# Power.net
KiCad netlist of a schematic drawn in Altium Designer
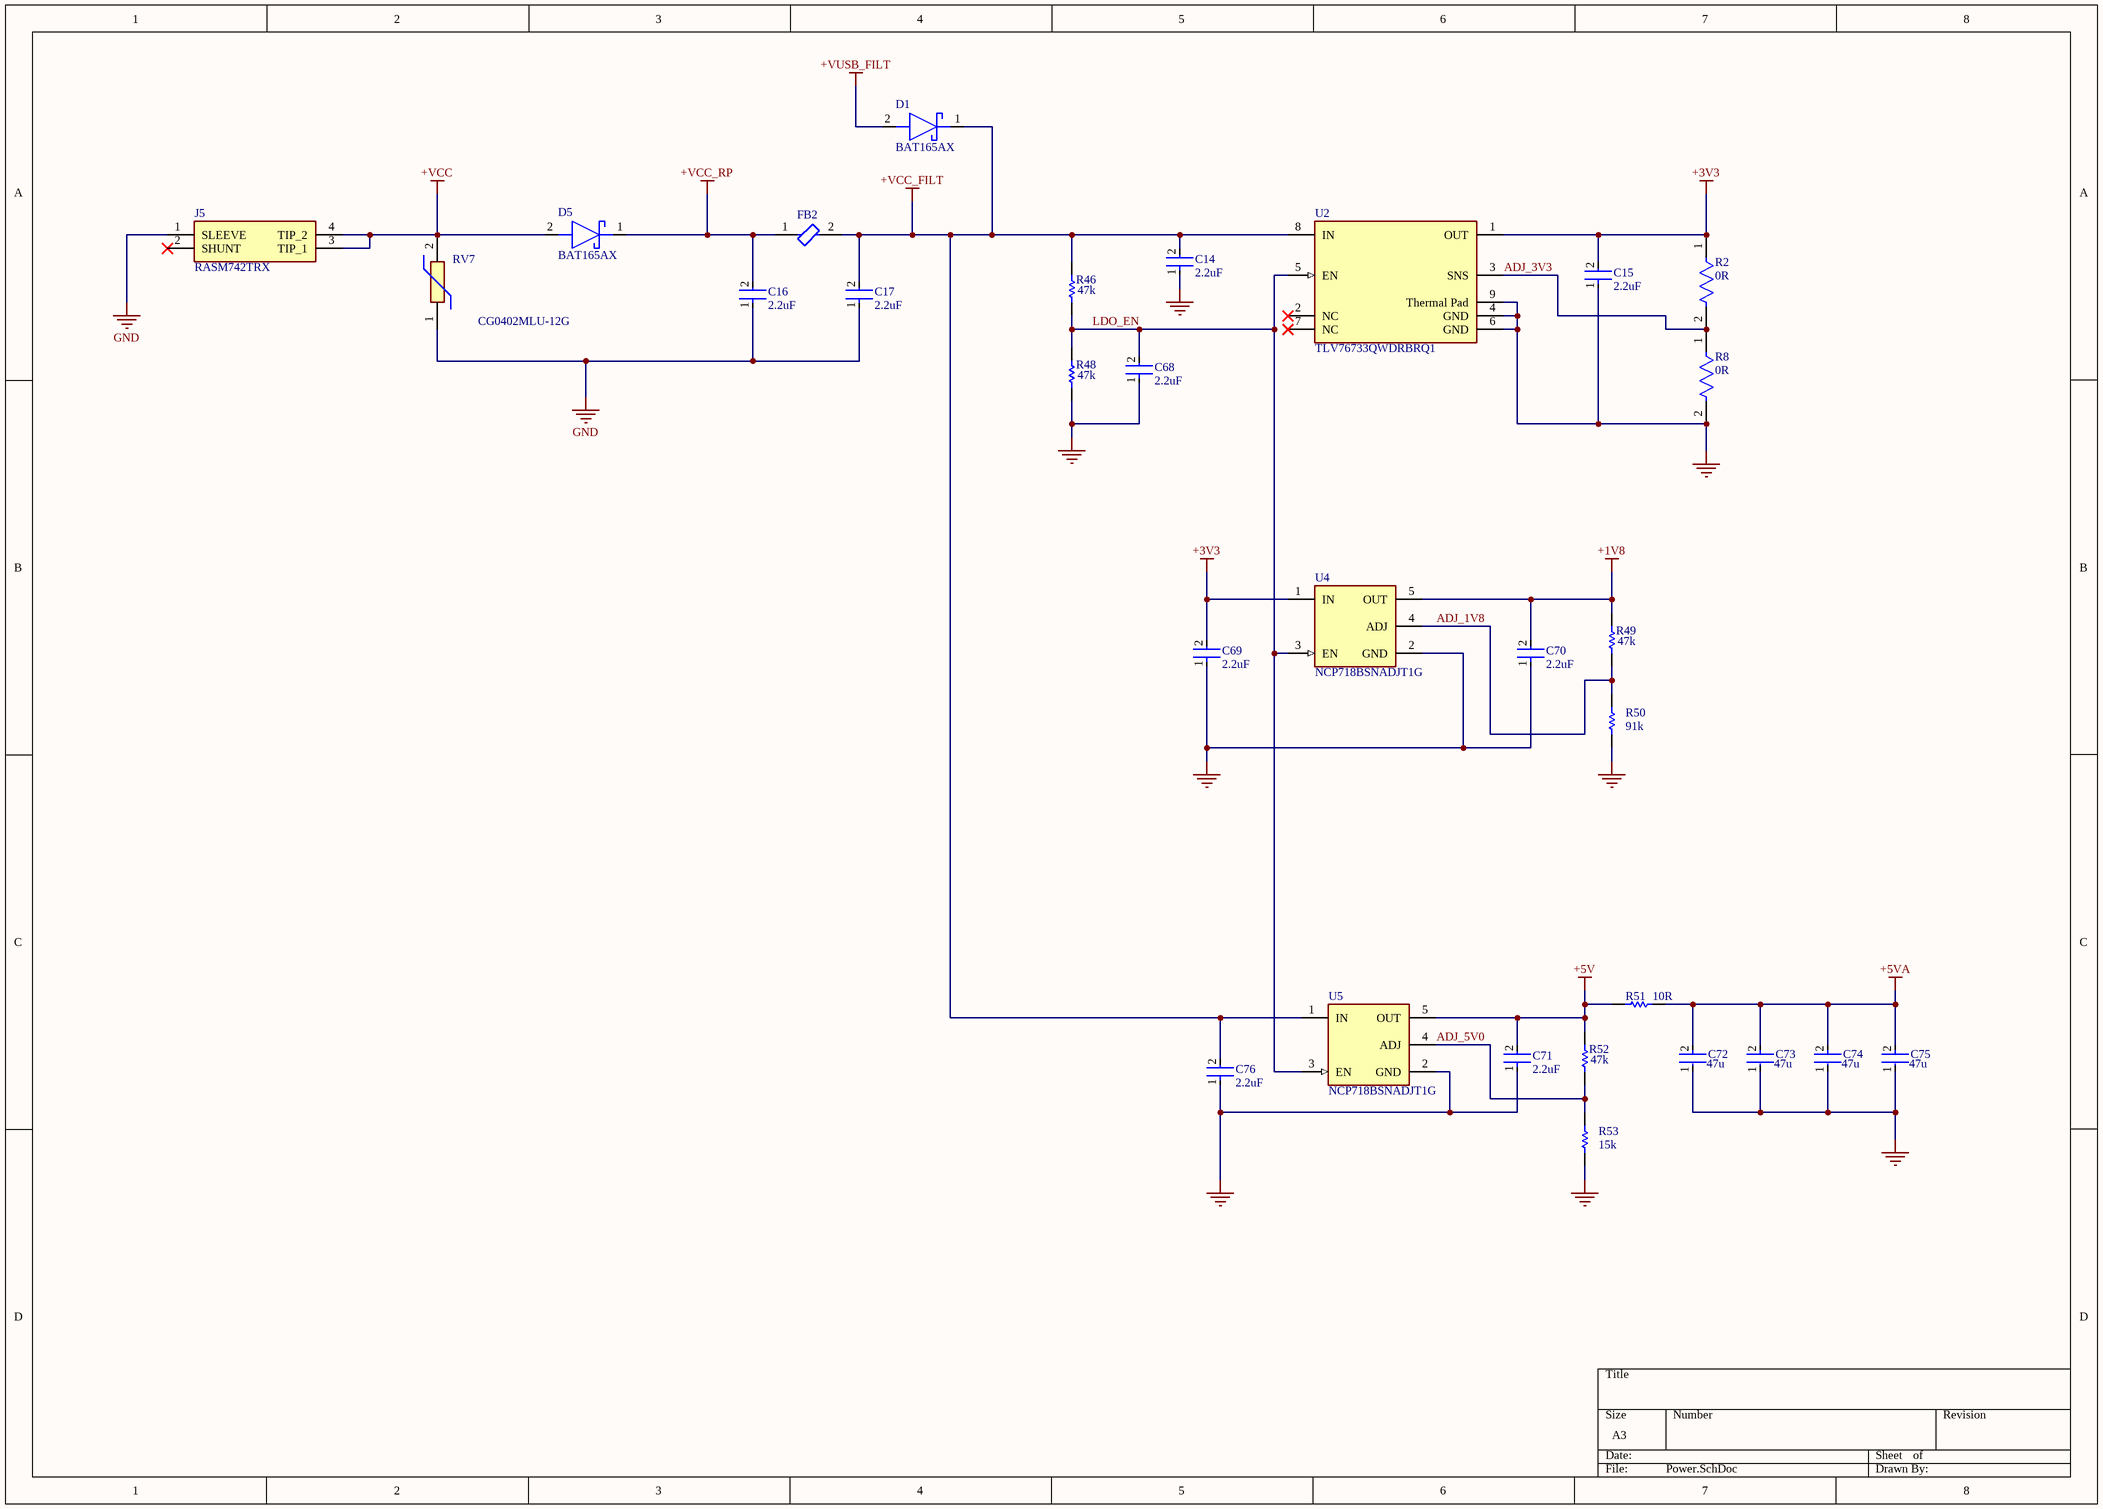
[diagram p0: Power.SchDoc]

(export (version "E")
  (design (tool "Eeschema 10.0.6"))
  (components
    (comp (ref "C14")
      (value "GCM188C71A225KE02D")
      (footprint "FP-GCH188-0_1-e0_2_0_5-MFG")
      (description "GCM188C71A225KE02D Multilayer Ceramic Capacitor, 2.2 uF, 10 V, ± 10%, X7S, 0603 [1608 Metric]")
      (fields (field (name "CAPACITANCE") "2.2uF"))
      (libsource (lib "Altium Content Vault") (part "b4654b650e69147ec39a6b967a45e02"))
    )
    (comp (ref "C15")
      (value "GCM188C71A225KE02D")
      (footprint "FP-GCH188-0_1-e0_2_0_5-MFG")
      (description "GCM188C71A225KE02D Multilayer Ceramic Capacitor, 2.2 uF, 10 V, ± 10%, X7S, 0603 [1608 Metric]")
      (fields (field (name "CAPACITANCE") "2.2uF"))
      (libsource (lib "Altium Content Vault") (part "b4654b650e69147ec39a6b967a45e02"))
    )
    (comp (ref "C16")
      (value "GCM188C71A225KE02D")
      (footprint "FP-GCH188-0_1-e0_2_0_5-MFG")
      (description "GCM188C71A225KE02D Multilayer Ceramic Capacitor, 2.2 uF, 10 V, ± 10%, X7S, 0603 [1608 Metric]")
      (fields (field (name "CAPACITANCE") "2.2uF"))
      (libsource (lib "Altium Content Vault") (part "b4654b650e69147ec39a6b967a45e02"))
    )
    (comp (ref "C17")
      (value "GCM188C71A225KE02D")
      (footprint "FP-GCH188-0_1-e0_2_0_5-MFG")
      (description "GCM188C71A225KE02D Multilayer Ceramic Capacitor, 2.2 uF, 10 V, ± 10%, X7S, 0603 [1608 Metric]")
      (fields (field (name "CAPACITANCE") "2.2uF"))
      (libsource (lib "Altium Content Vault") (part "b4654b650e69147ec39a6b967a45e02"))
    )
    (comp (ref "C68")
      (value "GCM188C71A225KE02D")
      (footprint "FP-GCH188-0_1-e0_2_0_5-MFG")
      (description "GCM188C71A225KE02D Multilayer Ceramic Capacitor, 2.2 uF, 10 V, ± 10%, X7S, 0603 [1608 Metric]")
      (fields (field (name "CAPACITANCE") "2.2uF"))
      (libsource (lib "Altium Content Vault") (part "b4654b650e69147ec39a6b967a45e02"))
    )
    (comp (ref "C69")
      (value "GCM188C71A225KE02D")
      (footprint "FP-GCH188-0_1-e0_2_0_5-MFG")
      (description "GCM188C71A225KE02D Multilayer Ceramic Capacitor, 2.2 uF, 10 V, ± 10%, X7S, 0603 [1608 Metric]")
      (fields (field (name "CAPACITANCE") "2.2uF"))
      (libsource (lib "Altium Content Vault") (part "b4654b650e69147ec39a6b967a45e02"))
    )
    (comp (ref "C70")
      (value "GCM188C71A225KE02D")
      (footprint "FP-GCH188-0_1-e0_2_0_5-MFG")
      (description "GCM188C71A225KE02D Multilayer Ceramic Capacitor, 2.2 uF, 10 V, ± 10%, X7S, 0603 [1608 Metric]")
      (fields (field (name "CAPACITANCE") "2.2uF"))
      (libsource (lib "Altium Content Vault") (part "b4654b650e69147ec39a6b967a45e02"))
    )
    (comp (ref "C71")
      (value "GCM188C71A225KE02D")
      (footprint "FP-GCH188-0_1-e0_2_0_5-MFG")
      (description "GCM188C71A225KE02D Multilayer Ceramic Capacitor, 2.2 uF, 10 V, ± 10%, X7S, 0603 [1608 Metric]")
      (fields (field (name "CAPACITANCE") "2.2uF"))
      (libsource (lib "Altium Content Vault") (part "b4654b650e69147ec39a6b967a45e02"))
    )
    (comp (ref "C72")
      (value "GCM32EC71A476KE02K")
      (footprint "FP-GCM32E-0_3-MFG")
      (description "Ceramic Capacitor for Automotive 47uF ±10% 10VDC X7S 1210 Embossed T/R")
      (fields (field (name "CAPACITANCE") "47u"))
      (libsource (lib "Altium Content Vault") (part "f23184f103b6ebe33a8c269c53dcba6"))
    )
    (comp (ref "C73")
      (value "GCM32EC71A476KE02K")
      (footprint "FP-GCM32E-0_3-MFG")
      (description "Ceramic Capacitor for Automotive 47uF ±10% 10VDC X7S 1210 Embossed T/R")
      (fields (field (name "CAPACITANCE") "47u"))
      (libsource (lib "Altium Content Vault") (part "f23184f103b6ebe33a8c269c53dcba6"))
    )
    (comp (ref "C74")
      (value "GCM32EC71A476KE02K")
      (footprint "FP-GCM32E-0_3-MFG")
      (description "Ceramic Capacitor for Automotive 47uF ±10% 10VDC X7S 1210 Embossed T/R")
      (fields (field (name "CAPACITANCE") "47u"))
      (libsource (lib "Altium Content Vault") (part "f23184f103b6ebe33a8c269c53dcba6"))
    )
    (comp (ref "C75")
      (value "GCM32EC71A476KE02K")
      (footprint "FP-GCM32E-0_3-MFG")
      (description "Ceramic Capacitor for Automotive 47uF ±10% 10VDC X7S 1210 Embossed T/R")
      (fields (field (name "CAPACITANCE") "47u"))
      (libsource (lib "Altium Content Vault") (part "f23184f103b6ebe33a8c269c53dcba6"))
    )
    (comp (ref "C76")
      (value "GCM188C71A225KE02D")
      (footprint "FP-GCH188-0_1-e0_2_0_5-MFG")
      (description "GCM188C71A225KE02D Multilayer Ceramic Capacitor, 2.2 uF, 10 V, ± 10%, X7S, 0603 [1608 Metric]")
      (fields (field (name "CAPACITANCE") "2.2uF"))
      (libsource (lib "Altium Content Vault") (part "b4654b650e69147ec39a6b967a45e02"))
    )
    (comp (ref "D1")
      (value "BAT165AX")
      (footprint "BAT165AX")
      (description "Schottky Diode")
      (fields (field (name "MOUSER PART NUMBER") "771-BAT165AX"))
      (libsource (lib "audio_dev_pcb") (part "BAT165AX"))
    )
    (comp (ref "D5")
      (value "BAT165AX")
      (footprint "BAT165AX")
      (description "Schottky Diode")
      (fields (field (name "MOUSER PART NUMBER") "771-BAT165AX"))
      (libsource (lib "audio_dev_pcb") (part "BAT165AX"))
    )
    (comp (ref "FB2")
      (value "MPZ1005S121ET000")
      (footprint "FP-MPZ1005-MFG")
      (description "Power line Ferrite Bead 120Ω @ 100MHz 1.5A DCR 0.095Ω SMD 0402")
      (fields (field (name "TOLERANCE") "25%"))
      (libsource (lib "Altium Content Vault") (part "5f30dd21d616792df468990f7003faa"))
    )
    (comp (ref "J5")
      (value "RASM742TRX")
      (footprint "RASM742TRX")
      (description "Connector")
      (fields (field (name "MOUSER PART NUMBER") "502-RASM742TRX"))
      (libsource (lib "audio_dev_pcb") (part "RASM742TRX"))
    )
    (comp (ref "R2")
      (value "RMCF0402ZT0R00")
      (footprint "FP-RMCF0402-MFG")
      (description "RES 0 OHM JUMPER 1/16W 0402")
      (fields (field (name "RESISTANCE") "0R"))
      (libsource (lib "Altium Content Vault") (part "1029c3af85768c4190bb7ad29bc67b5"))
    )
    (comp (ref "R8")
      (value "RMCF0402ZT0R00")
      (footprint "FP-RMCF0402-MFG")
      (description "RES 0 OHM JUMPER 1/16W 0402")
      (fields (field (name "RESISTANCE") "0R"))
      (libsource (lib "Altium Content Vault") (part "1029c3af85768c4190bb7ad29bc67b5"))
    )
    (comp (ref "R46")
      (value "RC0402JR-0747KL")
      (footprint "RESC1005X40X25LL05T10")
      (fields (field (name "MANUFACTURER") "Yageo / Phycomp") (field (name "RESISTANCE") "47k"))
      (libsource (lib "Altium Content Vault") (part "RES"))
    )
    (comp (ref "R48")
      (value "RC0402JR-0747KL")
      (footprint "RESC1005X40X25LL05T10")
      (fields (field (name "MANUFACTURER") "Yageo / Phycomp") (field (name "RESISTANCE") "47k"))
      (libsource (lib "Altium Content Vault") (part "RES"))
    )
    (comp (ref "R49")
      (value "RC0402JR-0747KL")
      (footprint "RESC1005X40X25LL05T10")
      (fields (field (name "MANUFACTURER") "Yageo / Phycomp") (field (name "RESISTANCE") "47k"))
      (libsource (lib "Altium Content Vault") (part "RES"))
    )
    (comp (ref "R50")
      (value "RC0402JR-0791KL")
      (footprint "RESC1005X40X25LL05T10")
      (fields (field (name "MANUFACTURER") "Yageo / Phycomp") (field (name "RESISTANCE") "91k"))
      (libsource (lib "Altium Content Vault") (part "RES"))
    )
    (comp (ref "R51")
      (value "RC0603JR-1310RL")
      (footprint "RESC1608X55X25LL10T15")
      (fields (field (name "MANUFACTURER") "Yageo") (field (name "RESISTANCE") "10R"))
      (libsource (lib "Altium Content Vault") (part "RES"))
    )
    (comp (ref "R52")
      (value "RC0402JR-0747KL")
      (footprint "RESC1005X40X25LL05T10")
      (fields (field (name "MANUFACTURER") "Yageo / Phycomp") (field (name "RESISTANCE") "47k"))
      (libsource (lib "Altium Content Vault") (part "RES"))
    )
    (comp (ref "R53")
      (value "RC0402JR-0715KL")
      (footprint "RESC1005X40X25NL05T10")
      (fields (field (name "MANUFACTURER") "Yageo / Phycomp") (field (name "RESISTANCE") "15k"))
      (libsource (lib "Altium Content Vault") (part "RES"))
    )
    (comp (ref "RV7")
      (value "CG0402MLU-12G")
      (footprint "VARC1005X41N")
      (description "Varistor")
      (fields (field (name "MOUSER PART NUMBER") "652-CG0402MLU-12G"))
      (libsource (lib "audio_dev_pcb") (part "CG0402MLU-12G"))
    )
    (comp (ref "U2")
      (value "TLV76733QWDRBRQ1")
      (footprint "FP-DRB0008J-IPC_C")
      (description "IC OPAMP")
      (libsource (lib "Altium Content Vault") (part "986f8d1759350ee61d4b04c225c65ee"))
    )
    (comp (ref "U4")
      (value "NCP718BSNADJT1G")
      (footprint "FP-419AE-01-IPC_C")
      (description "300 MA LOW IQ WIDE INPUT")
      (fields
        (field (name "OCTOPART") "https://octopart.com/ncp718bsnadjt1g-on+semiconductor-87658781")
        (field (name "MANUFACTURER") "On Semiconductor")
      )
      (libsource (lib "Altium Content Vault") (part "60dd149d16d23ee5a651c2107203ec7"))
    )
    (comp (ref "U5")
      (value "NCP718BSNADJT1G")
      (footprint "FP-419AE-01-IPC_C")
      (description "300 MA LOW IQ WIDE INPUT")
      (fields
        (field (name "OCTOPART") "https://octopart.com/ncp718bsnadjt1g-on+semiconductor-87658781")
        (field (name "MANUFACTURER") "On Semiconductor")
      )
      (libsource (lib "Altium Content Vault") (part "60dd149d16d23ee5a651c2107203ec7"))
    )
  )
  (nets
    (net (code "1") (name "+1V8") (class "Default")
      (node (ref "C70") (pin "2") (pinfunction "2_2") (pintype "passive"))
      (node (ref "R49") (pin "2") (pinfunction "2_2") (pintype "passive"))
      (node (ref "U4") (pin "5") (pinfunction "OUT_5") (pintype "power_in"))
    )
    (net (code "2") (name "+3V3") (class "Default")
      (node (ref "C15") (pin "2") (pinfunction "2_2") (pintype "passive"))
      (node (ref "C69") (pin "2") (pinfunction "2_2") (pintype "passive"))
      (node (ref "R2") (pin "1") (pinfunction "1_1") (pintype "passive"))
      (node (ref "U2") (pin "1") (pinfunction "OUT_1") (pintype "power_in"))
      (node (ref "U4") (pin "1") (pinfunction "IN_1") (pintype "power_in"))
    )
    (net (code "3") (name "+5V") (class "Default")
      (node (ref "C71") (pin "2") (pinfunction "2_2") (pintype "passive"))
      (node (ref "R51") (pin "1") (pinfunction "1_1") (pintype "passive"))
      (node (ref "R52") (pin "2") (pinfunction "2_2") (pintype "passive"))
      (node (ref "U5") (pin "5") (pinfunction "OUT_5") (pintype "power_in"))
    )
    (net (code "4") (name "+5VA") (class "Default")
      (node (ref "C72") (pin "2") (pinfunction "2_2") (pintype "passive"))
      (node (ref "C73") (pin "2") (pinfunction "2_2") (pintype "passive"))
      (node (ref "C74") (pin "2") (pinfunction "2_2") (pintype "passive"))
      (node (ref "C75") (pin "2") (pinfunction "2_2") (pintype "passive"))
      (node (ref "R51") (pin "2") (pinfunction "2_2") (pintype "passive"))
    )
    (net (code "5") (name "+VCC") (class "Default")
      (node (ref "D5") (pin "2") (pinfunction "A_2") (pintype "passive"))
      (node (ref "J5") (pin "3") (pinfunction "TIP_1_3") (pintype "passive"))
      (node (ref "J5") (pin "4") (pinfunction "TIP_2_4") (pintype "passive"))
      (node (ref "RV7") (pin "2") (pinfunction "2_2") (pintype "passive"))
    )
    (net (code "6") (name "+VCC_FILT") (class "Default")
      (node (ref "C14") (pin "2") (pinfunction "2_2") (pintype "passive"))
      (node (ref "C17") (pin "2") (pinfunction "2_2") (pintype "passive"))
      (node (ref "C76") (pin "2") (pinfunction "2_2") (pintype "passive"))
      (node (ref "D1") (pin "1") (pinfunction "K_1") (pintype "passive"))
      (node (ref "FB2") (pin "2") (pinfunction "2_2") (pintype "passive"))
      (node (ref "R46") (pin "2") (pinfunction "2_2") (pintype "passive"))
      (node (ref "U2") (pin "8") (pinfunction "IN_8") (pintype "power_in"))
      (node (ref "U5") (pin "1") (pinfunction "IN_1") (pintype "power_in"))
    )
    (net (code "7") (name "+VCC_RP") (class "Default")
      (node (ref "C16") (pin "2") (pinfunction "2_2") (pintype "passive"))
      (node (ref "D5") (pin "1") (pinfunction "K_1") (pintype "passive"))
      (node (ref "FB2") (pin "1") (pinfunction "1_1") (pintype "passive"))
    )
    (net (code "8") (name "+VUSB_FILT") (class "Default")
      (node (ref "D1") (pin "2") (pinfunction "A_2") (pintype "passive"))
    )
    (net (code "9") (name "/ADJ_1V8") (class "Default")
      (node (ref "R49") (pin "1") (pinfunction "1_1") (pintype "passive"))
      (node (ref "R50") (pin "2") (pinfunction "2_2") (pintype "passive"))
      (node (ref "U4") (pin "4") (pinfunction "ADJ_4") (pintype "passive"))
    )
    (net (code "10") (name "/ADJ_3V3") (class "Default")
      (node (ref "R2") (pin "2") (pinfunction "2_2") (pintype "passive"))
      (node (ref "R8") (pin "1") (pinfunction "1_1") (pintype "passive"))
      (node (ref "U2") (pin "3") (pinfunction "SNS_3") (pintype "passive"))
    )
    (net (code "11") (name "/ADJ_5V0") (class "Default")
      (node (ref "R52") (pin "1") (pinfunction "1_1") (pintype "passive"))
      (node (ref "R53") (pin "2") (pinfunction "2_2") (pintype "passive"))
      (node (ref "U5") (pin "4") (pinfunction "ADJ_4") (pintype "passive"))
    )
    (net (code "12") (name "/LDO_EN") (class "Default")
      (node (ref "C68") (pin "2") (pinfunction "2_2") (pintype "passive"))
      (node (ref "R46") (pin "1") (pinfunction "1_1") (pintype "passive"))
      (node (ref "R48") (pin "2") (pinfunction "2_2") (pintype "passive"))
      (node (ref "U2") (pin "5") (pinfunction "EN_5") (pintype "input"))
      (node (ref "U4") (pin "3") (pinfunction "EN_3") (pintype "input"))
      (node (ref "U5") (pin "3") (pinfunction "EN_3") (pintype "input"))
    )
    (net (code "13") (name "GND") (class "Default")
      (node (ref "C14") (pin "1") (pinfunction "1_1") (pintype "passive"))
      (node (ref "C15") (pin "1") (pinfunction "1_1") (pintype "passive"))
      (node (ref "C16") (pin "1") (pinfunction "1_1") (pintype "passive"))
      (node (ref "C17") (pin "1") (pinfunction "1_1") (pintype "passive"))
      (node (ref "C68") (pin "1") (pinfunction "1_1") (pintype "passive"))
      (node (ref "C69") (pin "1") (pinfunction "1_1") (pintype "passive"))
      (node (ref "C70") (pin "1") (pinfunction "1_1") (pintype "passive"))
      (node (ref "C71") (pin "1") (pinfunction "1_1") (pintype "passive"))
      (node (ref "C72") (pin "1") (pinfunction "1_1") (pintype "passive"))
      (node (ref "C73") (pin "1") (pinfunction "1_1") (pintype "passive"))
      (node (ref "C74") (pin "1") (pinfunction "1_1") (pintype "passive"))
      (node (ref "C75") (pin "1") (pinfunction "1_1") (pintype "passive"))
      (node (ref "C76") (pin "1") (pinfunction "1_1") (pintype "passive"))
      (node (ref "J5") (pin "1") (pinfunction "SLEEVE_1") (pintype "passive"))
      (node (ref "R48") (pin "1") (pinfunction "1_1") (pintype "passive"))
      (node (ref "R50") (pin "1") (pinfunction "1_1") (pintype "passive"))
      (node (ref "R53") (pin "1") (pinfunction "1_1") (pintype "passive"))
      (node (ref "R8") (pin "2") (pinfunction "2_2") (pintype "passive"))
      (node (ref "RV7") (pin "1") (pinfunction "1_1") (pintype "passive"))
      (node (ref "U2") (pin "4") (pinfunction "GND_4") (pintype "power_in"))
      (node (ref "U2") (pin "6") (pinfunction "GND_6") (pintype "power_in"))
      (node (ref "U2") (pin "9") (pinfunction "Thermal_Pad_9") (pintype "passive"))
      (node (ref "U4") (pin "2") (pinfunction "GND_2") (pintype "power_in"))
      (node (ref "U5") (pin "2") (pinfunction "GND_2") (pintype "power_in"))
    )
    (net (code "14") (name "unconnected-(J5-SHUNT-Pad2)") (class "Default")
      (node (ref "J5") (pin "2") (pinfunction "SHUNT_2") (pintype "passive+no_connect"))
    )
    (net (code "15") (name "unconnected-(U2-NC-Pad2)") (class "Default")
      (node (ref "U2") (pin "2") (pinfunction "NC_2") (pintype "passive+no_connect"))
    )
    (net (code "16") (name "unconnected-(U2-NC-Pad7)") (class "Default")
      (node (ref "U2") (pin "7") (pinfunction "NC_7") (pintype "passive+no_connect"))
    )
  )
)
